# schematicEagle.net
KiCad netlist of a schematic drawn in EAGLE
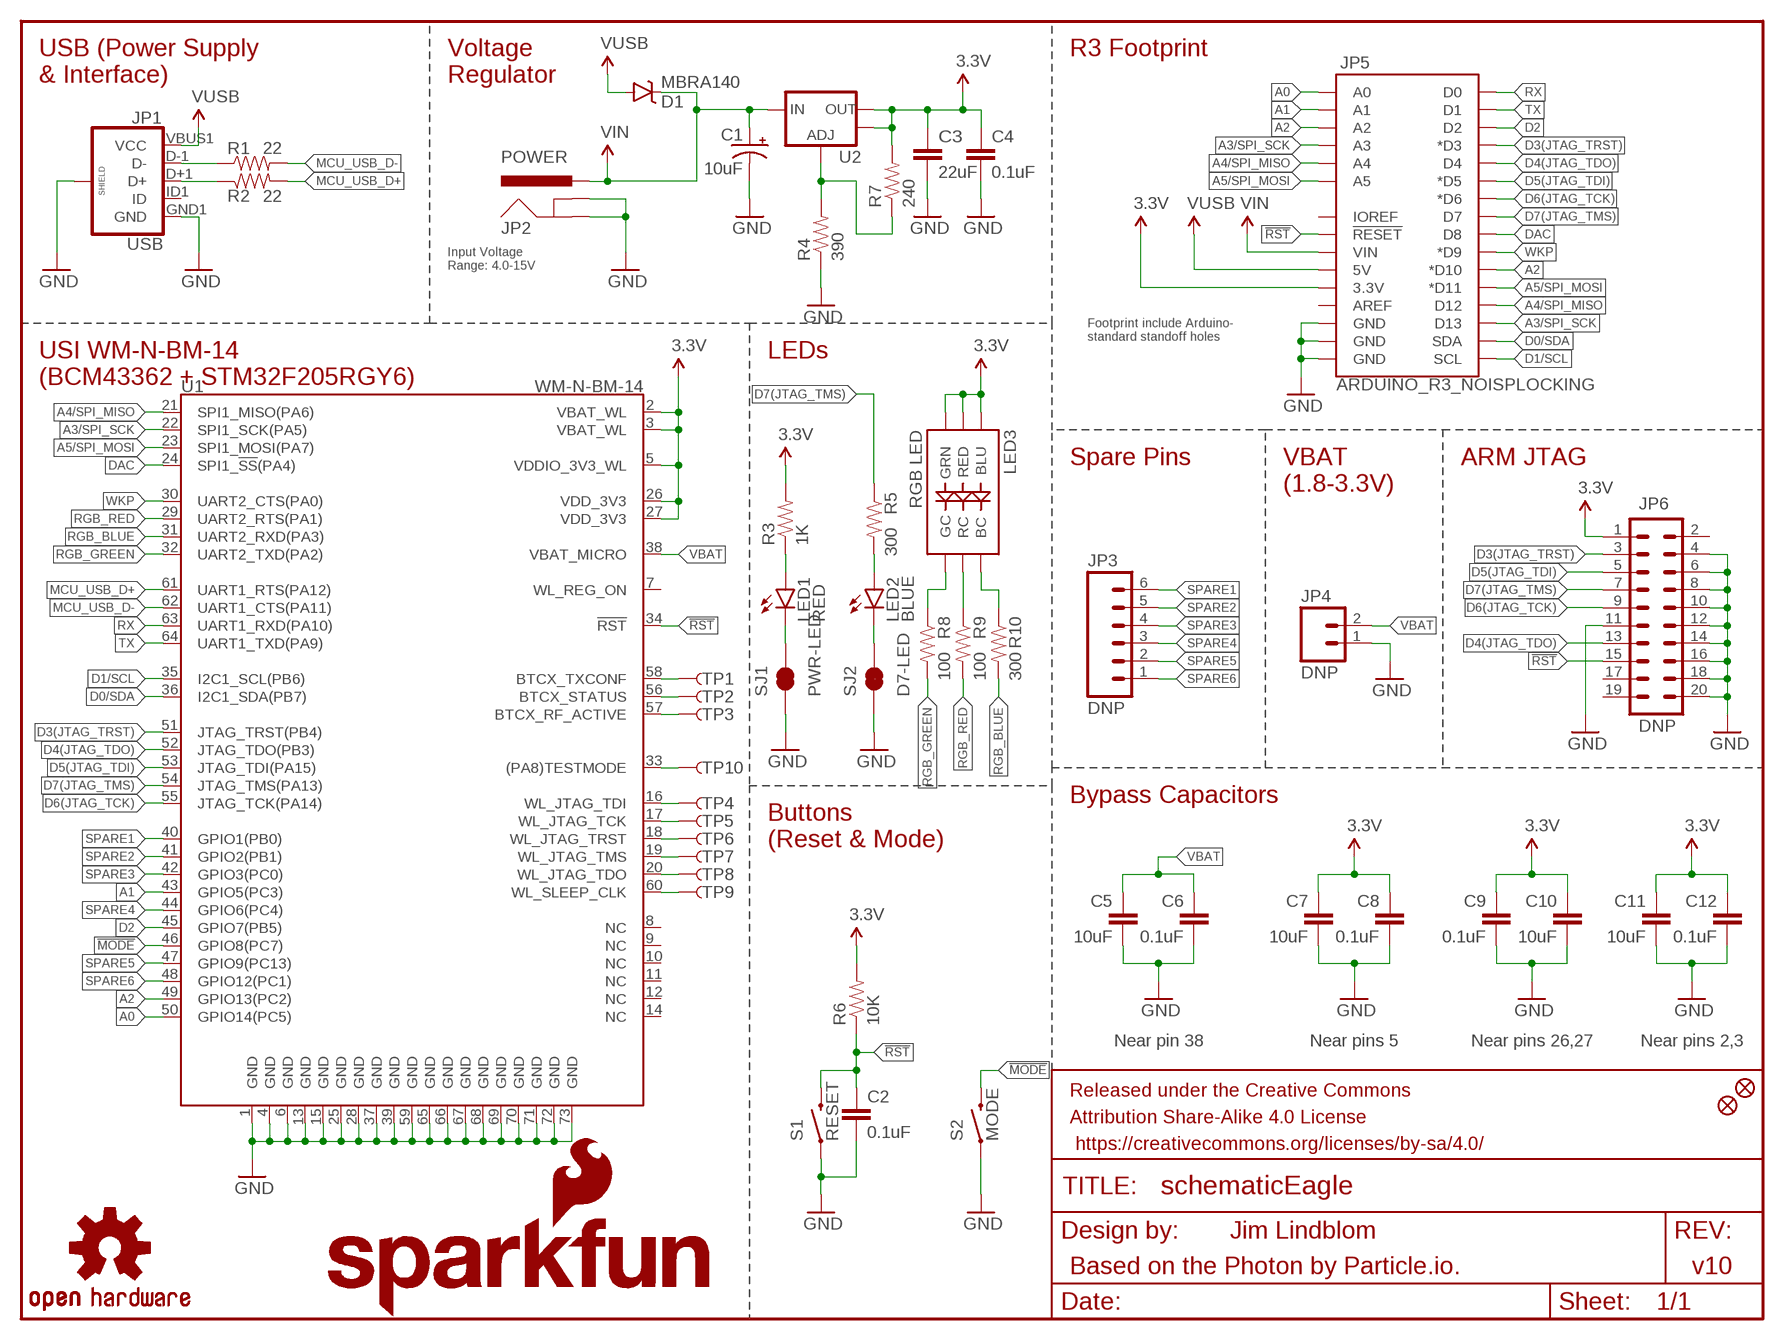
[diagram p0: schematic, sheet 1]

(export (version "E")
  (design (tool "Eeschema 10.0.6"))
  (components
    (comp (ref "C1")
      (value "10uF")
      (footprint "eagle-import:EIA3216")
      (libsource (lib "eagle-import") (part "10UF-16V-10%(TANT)"))
    )
    (comp (ref "C2")
      (value "0.1uF")
      (footprint "eagle-import:0603-CAP")
      (libsource (lib "eagle-import") (part "0.1UF-25V(+80/-20%)(0603)"))
    )
    (comp (ref "C3")
      (value "22uF")
      (footprint "eagle-import:0805")
      (libsource (lib "eagle-import") (part "22UF-6.3V-20%(0805)"))
    )
    (comp (ref "C4")
      (value "0.1uF")
      (footprint "eagle-import:0603-CAP")
      (libsource (lib "eagle-import") (part "0.1UF-25V(+80/-20%)(0603)"))
    )
    (comp (ref "C5")
      (value "10uF")
      (footprint "eagle-import:0603-CAP")
      (libsource (lib "eagle-import") (part "10UF-6.3V-20%(0603)"))
    )
    (comp (ref "C6")
      (value "0.1uF")
      (footprint "eagle-import:0603-CAP")
      (libsource (lib "eagle-import") (part "0.1UF-25V(+80/-20%)(0603)"))
    )
    (comp (ref "C7")
      (value "10uF")
      (footprint "eagle-import:0603-CAP")
      (libsource (lib "eagle-import") (part "10UF-6.3V-20%(0603)"))
    )
    (comp (ref "C8")
      (value "0.1uF")
      (footprint "eagle-import:0603-CAP")
      (libsource (lib "eagle-import") (part "0.1UF-25V(+80/-20%)(0603)"))
    )
    (comp (ref "C9")
      (value "0.1uF")
      (footprint "eagle-import:0603-CAP")
      (libsource (lib "eagle-import") (part "0.1UF-25V(+80/-20%)(0603)"))
    )
    (comp (ref "C10")
      (value "10uF")
      (footprint "eagle-import:0603-CAP")
      (libsource (lib "eagle-import") (part "10UF-6.3V-20%(0603)"))
    )
    (comp (ref "C11")
      (value "10uF")
      (footprint "eagle-import:0603-CAP")
      (libsource (lib "eagle-import") (part "10UF-6.3V-20%(0603)"))
    )
    (comp (ref "C12")
      (value "0.1uF")
      (footprint "eagle-import:0603-CAP")
      (libsource (lib "eagle-import") (part "0.1UF-25V(+80/-20%)(0603)"))
    )
    (comp (ref "D1")
      (value "MBRA140")
      (footprint "eagle-import:SMA-DIODE")
      (libsource (lib "eagle-import") (part "DIODE-SCHOTTKY-MBRA140"))
    )
    (comp (ref "FID1")
      (value "FIDUCIAL1X2")
      (footprint "eagle-import:FIDUCIAL-1X2")
      (libsource (lib "eagle-import") (part "FIDUCIAL1X2"))
    )
    (comp (ref "FID2")
      (value "FIDUCIAL1X2")
      (footprint "eagle-import:FIDUCIAL-1X2")
      (libsource (lib "eagle-import") (part "FIDUCIAL1X2"))
    )
    (comp (ref "FRAME1")
      (value "FRAME-LETTER")
      (footprint "eagle-import:CREATIVE_COMMONS")
      (fields (field (name "DESIGNER") "Jim Lindblom"))
      (libsource (lib "eagle-import") (part "FRAME-LETTER"))
    )
    (comp (ref "JP1")
      (value "USB")
      (footprint "eagle-import:USB-B-MICRO-SMD_V03")
      (libsource (lib "eagle-import") (part "USB_MICROB_PLUGCONN-11752"))
    )
    (comp (ref "JP2")
      (value "POWER")
      (footprint "eagle-import:POWER_JACK_PTH_LOCK")
      (libsource (lib "eagle-import") (part "POWER_JACKPTH_LOCK"))
    )
    (comp (ref "JP3")
      (value "DNP")
      (footprint "eagle-import:1X06")
      (libsource (lib "eagle-import") (part "M06SILK_FEMALE_PTH"))
    )
    (comp (ref "JP4")
      (value "DNP")
      (footprint "eagle-import:1X02")
      (libsource (lib "eagle-import") (part "M02PTH"))
    )
    (comp (ref "JP5")
      (value "ARDUINO_R3_NOISPLOCKING")
      (footprint "eagle-import:ARDUINO_R3_NOISP_LOCKING")
      (libsource (lib "eagle-import") (part "ARDUINO_R3_NOISPLOCKING"))
    )
    (comp (ref "JP6")
      (value "DNP")
      (footprint "eagle-import:2X10")
      (libsource (lib "eagle-import") (part "M10X2"))
    )
    (comp (ref "LED1")
      (value "RED")
      (footprint "eagle-import:LED-1206")
      (libsource (lib "eagle-import") (part "LED-RED1206"))
    )
    (comp (ref "LED2")
      (value "BLUE")
      (footprint "eagle-import:LED-1206")
      (libsource (lib "eagle-import") (part "LED-BLUE1206"))
    )
    (comp (ref "LED3")
      (value "RGB LED")
      (footprint "eagle-import:PLCC-6-LED")
      (libsource (lib "eagle-import") (part "LED-TRICOLOR-NO-COMPLCC-6-SMD"))
    )
    (comp (ref "LOGO1")
      (value "OSHW-LOGOM")
      (footprint "eagle-import:OSHW-LOGO-M")
      (libsource (lib "eagle-import") (part "OSHW-LOGOM"))
    )
    (comp (ref "LOGO2")
      (value "SFE_LOGO_NAME_FLAME.2_INCH")
      (footprint "eagle-import:SFE_LOGO_NAME_FLAME_.2")
      (libsource (lib "eagle-import") (part "SFE_LOGO_NAME_FLAME.2_INCH"))
    )
    (comp (ref "LOGO3")
      (value "SFE_LOGO_NAME_FLAME.4_INCH")
      (footprint "eagle-import:SFE_LOGO_NAME_FLAME_.4")
      (libsource (lib "eagle-import") (part "SFE_LOGO_NAME_FLAME.4_INCH"))
    )
    (comp (ref "R1")
      (value "22")
      (footprint "eagle-import:0603-RES")
      (libsource (lib "eagle-import") (part "22OHM1/10W1%(0603)"))
    )
    (comp (ref "R2")
      (value "22")
      (footprint "eagle-import:0603-RES")
      (libsource (lib "eagle-import") (part "22OHM1/10W1%(0603)"))
    )
    (comp (ref "R3")
      (value "1K")
      (footprint "eagle-import:0603-RES")
      (libsource (lib "eagle-import") (part "1KOHM-1/10W-1%(0603)"))
    )
    (comp (ref "R4")
      (value "390")
      (footprint "eagle-import:0603-RES")
      (libsource (lib "eagle-import") (part "390OHM1/10W1%(0603)"))
    )
    (comp (ref "R5")
      (value "300")
      (footprint "eagle-import:0603-RES")
      (libsource (lib "eagle-import") (part "300OHM-1/10W-1%(0603)"))
    )
    (comp (ref "R6")
      (value "10K")
      (footprint "eagle-import:0603-RES")
      (libsource (lib "eagle-import") (part "10KOHM-1/10W-1%(0603)0603"))
    )
    (comp (ref "R7")
      (value "240")
      (footprint "eagle-import:0603-RES")
      (libsource (lib "eagle-import") (part "240OHM1/10W1%(0603)"))
    )
    (comp (ref "R8")
      (value "100")
      (footprint "eagle-import:0603-RES")
      (libsource (lib "eagle-import") (part "100OHM-1/10W-1%(0603)"))
    )
    (comp (ref "R9")
      (value "100")
      (footprint "eagle-import:0603-RES")
      (libsource (lib "eagle-import") (part "100OHM-1/10W-1%(0603)"))
    )
    (comp (ref "R10")
      (value "300")
      (footprint "eagle-import:0603-RES")
      (libsource (lib "eagle-import") (part "300OHM-1/10W-1%(0603)"))
    )
    (comp (ref "S1")
      (value "RESET")
      (footprint "eagle-import:TACTILE-PTH")
      (libsource (lib "eagle-import") (part "SWITCH-MOMENTARY-2PTH"))
    )
    (comp (ref "S2")
      (value "MODE")
      (footprint "eagle-import:TACTILE-PTH")
      (libsource (lib "eagle-import") (part "SWITCH-MOMENTARY-2PTH"))
    )
    (comp (ref "SJ1")
      (value "PWR-LED")
      (footprint "eagle-import:PAD-JUMPER-2-NC_BY_TRACE_YES_SILK")
      (libsource (lib "eagle-import") (part "JUMPER-PAD-2-NC_BY_TRACE"))
    )
    (comp (ref "SJ2")
      (value "D7-LED")
      (footprint "eagle-import:PAD-JUMPER-2-NC_BY_TRACE_YES_SILK")
      (libsource (lib "eagle-import") (part "JUMPER-PAD-2-NC_BY_TRACE"))
    )
    (comp (ref "TP1")
      (value "TEST-POINTTP_15TH_THRU")
      (footprint "eagle-import:TP_15TH")
      (libsource (lib "eagle-import") (part "TEST-POINTTP_15TH_THRU"))
    )
    (comp (ref "TP2")
      (value "TEST-POINTTP_15TH_THRU")
      (footprint "eagle-import:TP_15TH")
      (libsource (lib "eagle-import") (part "TEST-POINTTP_15TH_THRU"))
    )
    (comp (ref "TP3")
      (value "TEST-POINTTP_15TH_THRU")
      (footprint "eagle-import:TP_15TH")
      (libsource (lib "eagle-import") (part "TEST-POINTTP_15TH_THRU"))
    )
    (comp (ref "TP4")
      (value "TEST-POINTTP_15TH_THRU")
      (footprint "eagle-import:TP_15TH")
      (libsource (lib "eagle-import") (part "TEST-POINTTP_15TH_THRU"))
    )
    (comp (ref "TP5")
      (value "TEST-POINTTP_15TH_THRU")
      (footprint "eagle-import:TP_15TH")
      (libsource (lib "eagle-import") (part "TEST-POINTTP_15TH_THRU"))
    )
    (comp (ref "TP6")
      (value "TEST-POINTTP_15TH_THRU")
      (footprint "eagle-import:TP_15TH")
      (libsource (lib "eagle-import") (part "TEST-POINTTP_15TH_THRU"))
    )
    (comp (ref "TP7")
      (value "TEST-POINTTP_15TH_THRU")
      (footprint "eagle-import:TP_15TH")
      (libsource (lib "eagle-import") (part "TEST-POINTTP_15TH_THRU"))
    )
    (comp (ref "TP8")
      (value "TEST-POINTTP_15TH_THRU")
      (footprint "eagle-import:TP_15TH")
      (libsource (lib "eagle-import") (part "TEST-POINTTP_15TH_THRU"))
    )
    (comp (ref "TP9")
      (value "TEST-POINTTP_15TH_THRU")
      (footprint "eagle-import:TP_15TH")
      (libsource (lib "eagle-import") (part "TEST-POINTTP_15TH_THRU"))
    )
    (comp (ref "TP10")
      (value "TEST-POINTTP_15TH_THRU")
      (footprint "eagle-import:TP_15TH")
      (libsource (lib "eagle-import") (part "TEST-POINTTP_15TH_THRU"))
    )
    (comp (ref "U1")
      (value "WM-N-BM-14")
      (footprint "eagle-import:WM-N-BM-14")
      (libsource (lib "eagle-import") (part "WM-N-BM-14"))
    )
    (comp (ref "U2")
      (value "V_REG_LM1117SOT223")
      (footprint "eagle-import:SOT223")
      (libsource (lib "eagle-import") (part "V_REG_LM1117SOT223"))
    )
  )
  (nets
    (net (code "1") (name "/~{MODE}") (class "Default")
      (node (ref "S2") (pin "3") (pinfunction "2_3") (pintype "passive"))
      (node (ref "U1") (pin "46") (pinfunction "GPIO8(PC7)_46") (pintype "bidirectional"))
    )
    (net (code "2") (name "/~{RST}") (class "Default")
      (node (ref "C2") (pin "1") (pinfunction "1_1") (pintype "passive"))
      (node (ref "JP5") (pin "RESET@1") (pinfunction "~{RESET}_RESET@1") (pintype "bidirectional"))
      (node (ref "JP6") (pin "15") (pinfunction "15_15") (pintype "passive"))
      (node (ref "R6") (pin "1") (pinfunction "1_1") (pintype "passive"))
      (node (ref "S1") (pin "3") (pinfunction "2_3") (pintype "passive"))
      (node (ref "U1") (pin "34") (pinfunction "~{RST}_34") (pintype "bidirectional"))
    )
    (net (code "3") (name "3.3V") (class "Default")
      (node (ref "C10") (pin "1") (pinfunction "1_1") (pintype "passive"))
      (node (ref "C11") (pin "1") (pinfunction "1_1") (pintype "passive"))
      (node (ref "C12") (pin "1") (pinfunction "1_1") (pintype "passive"))
      (node (ref "C3") (pin "1") (pinfunction "1_1") (pintype "passive"))
      (node (ref "C4") (pin "1") (pinfunction "1_1") (pintype "passive"))
      (node (ref "C7") (pin "1") (pinfunction "1_1") (pintype "passive"))
      (node (ref "C8") (pin "1") (pinfunction "1_1") (pintype "passive"))
      (node (ref "C9") (pin "1") (pinfunction "1_1") (pintype "passive"))
      (node (ref "JP5") (pin "3.3V") (pinfunction "3.3V_3.3V") (pintype "bidirectional"))
      (node (ref "JP6") (pin "1") (pinfunction "1_1") (pintype "passive"))
      (node (ref "LED3") (pin "AB") (pinfunction "BLU_AB") (pintype "bidirectional"))
      (node (ref "LED3") (pin "AG") (pinfunction "GRN_AG") (pintype "bidirectional"))
      (node (ref "LED3") (pin "AR") (pinfunction "RED_AR") (pintype "bidirectional"))
      (node (ref "R3") (pin "2") (pinfunction "2_2") (pintype "passive"))
      (node (ref "R6") (pin "2") (pinfunction "2_2") (pintype "passive"))
      (node (ref "R7") (pin "2") (pinfunction "2_2") (pintype "passive"))
      (node (ref "U1") (pin "2") (pinfunction "VBAT_WL_2") (pintype "bidirectional"))
      (node (ref "U1") (pin "26") (pinfunction "VDD_3V3_26") (pintype "bidirectional"))
      (node (ref "U1") (pin "27") (pinfunction "VDD_3V3_27") (pintype "bidirectional"))
      (node (ref "U1") (pin "3") (pinfunction "VBAT_WL_3") (pintype "bidirectional"))
      (node (ref "U1") (pin "5") (pinfunction "VDDIO_3V3_WL_5") (pintype "bidirectional"))
      (node (ref "U2") (pin "2") (pinfunction "OUT_2") (pintype "output"))
      (node (ref "U2") (pin "4") (pinfunction "OUT_4") (pintype "output"))
    )
    (net (code "4") (name "A0") (class "Default")
      (node (ref "JP5") (pin "A0") (pinfunction "A0_A0") (pintype "bidirectional"))
      (node (ref "U1") (pin "50") (pinfunction "GPIO14(PC5)_50") (pintype "bidirectional"))
    )
    (net (code "5") (name "A1") (class "Default")
      (node (ref "JP5") (pin "A1") (pinfunction "A1_A1") (pintype "bidirectional"))
      (node (ref "U1") (pin "43") (pinfunction "GPIO5(PC3)_43") (pintype "bidirectional"))
    )
    (net (code "6") (name "A2") (class "Default")
      (node (ref "JP5") (pin "A2") (pinfunction "A2_A2") (pintype "bidirectional"))
      (node (ref "JP5") (pin "D10") (pinfunction "*D10_D10") (pintype "bidirectional"))
      (node (ref "U1") (pin "49") (pinfunction "GPIO13(PC2)_49") (pintype "bidirectional"))
    )
    (net (code "7") (name "A3{slash}SPI_SCK") (class "Default")
      (node (ref "JP5") (pin "A3") (pinfunction "A3_A3") (pintype "bidirectional"))
      (node (ref "JP5") (pin "D13") (pinfunction "D13_D13") (pintype "bidirectional"))
      (node (ref "U1") (pin "22") (pinfunction "SPI1_SCK(PA5)_22") (pintype "bidirectional"))
    )
    (net (code "8") (name "A4{slash}SPI_MISO") (class "Default")
      (node (ref "JP5") (pin "A4") (pinfunction "A4_A4") (pintype "bidirectional"))
      (node (ref "JP5") (pin "D12") (pinfunction "D12_D12") (pintype "bidirectional"))
      (node (ref "U1") (pin "21") (pinfunction "SPI1_MISO(PA6)_21") (pintype "bidirectional"))
    )
    (net (code "9") (name "A5{slash}SPI_MOSI") (class "Default")
      (node (ref "JP5") (pin "A5") (pinfunction "A5_A5") (pintype "bidirectional"))
      (node (ref "JP5") (pin "D11") (pinfunction "*D11_D11") (pintype "bidirectional"))
      (node (ref "U1") (pin "23") (pinfunction "SPI1_MOSI(PA7)_23") (pintype "bidirectional"))
    )
    (net (code "10") (name "D0{slash}SDA") (class "Default")
      (node (ref "JP5") (pin "SDA") (pinfunction "SDA_SDA") (pintype "bidirectional"))
      (node (ref "U1") (pin "36") (pinfunction "I2C1_SDA(PB7)_36") (pintype "bidirectional"))
    )
    (net (code "11") (name "D1{slash}SCL") (class "Default")
      (node (ref "JP5") (pin "SCL") (pinfunction "SCL_SCL") (pintype "bidirectional"))
      (node (ref "U1") (pin "35") (pinfunction "I2C1_SCL(PB6)_35") (pintype "bidirectional"))
    )
    (net (code "12") (name "D2") (class "Default")
      (node (ref "JP5") (pin "D2") (pinfunction "D2_D2") (pintype "bidirectional"))
      (node (ref "U1") (pin "45") (pinfunction "GPIO7(PB5)_45") (pintype "bidirectional"))
    )
    (net (code "13") (name "D3(JTAG_TRST)") (class "Default")
      (node (ref "JP5") (pin "D3") (pinfunction "*D3_D3") (pintype "bidirectional"))
      (node (ref "JP6") (pin "3") (pinfunction "3_3") (pintype "passive"))
      (node (ref "U1") (pin "51") (pinfunction "JTAG_TRST(PB4)_51") (pintype "bidirectional"))
    )
    (net (code "14") (name "D4(JTAG_TDO)") (class "Default")
      (node (ref "JP5") (pin "D4") (pinfunction "D4_D4") (pintype "bidirectional"))
      (node (ref "JP6") (pin "13") (pinfunction "13_13") (pintype "passive"))
      (node (ref "U1") (pin "52") (pinfunction "JTAG_TDO(PB3)_52") (pintype "bidirectional"))
    )
    (net (code "15") (name "D5(JTAG_TDI)") (class "Default")
      (node (ref "JP5") (pin "D5") (pinfunction "*D5_D5") (pintype "bidirectional"))
      (node (ref "JP6") (pin "5") (pinfunction "5_5") (pintype "passive"))
      (node (ref "U1") (pin "53") (pinfunction "JTAG_TDI(PA15)_53") (pintype "bidirectional"))
    )
    (net (code "16") (name "D6(JTAG_TCK)") (class "Default")
      (node (ref "JP5") (pin "D6") (pinfunction "*D6_D6") (pintype "bidirectional"))
      (node (ref "JP6") (pin "9") (pinfunction "9_9") (pintype "passive"))
      (node (ref "U1") (pin "55") (pinfunction "JTAG_TCK(PA14)_55") (pintype "bidirectional"))
    )
    (net (code "17") (name "D7(JTAG_TMS)") (class "Default")
      (node (ref "JP5") (pin "D7") (pinfunction "D7_D7") (pintype "bidirectional"))
      (node (ref "JP6") (pin "7") (pinfunction "7_7") (pintype "passive"))
      (node (ref "R5") (pin "1") (pinfunction "1_1") (pintype "passive"))
      (node (ref "U1") (pin "54") (pinfunction "JTAG_TMS(PA13)_54") (pintype "bidirectional"))
    )
    (net (code "18") (name "DAC") (class "Default")
      (node (ref "JP5") (pin "D8") (pinfunction "D8_D8") (pintype "bidirectional"))
      (node (ref "U1") (pin "24") (pinfunction "SPI1_~{SS}(PA4)_24") (pintype "bidirectional"))
    )
    (net (code "19") (name "GND") (class "Default")
      (node (ref "C1") (pin "C") (pinfunction "-_C") (pintype "passive"))
      (node (ref "C10") (pin "2") (pinfunction "2_2") (pintype "passive"))
      (node (ref "C11") (pin "2") (pinfunction "2_2") (pintype "passive"))
      (node (ref "C12") (pin "2") (pinfunction "2_2") (pintype "passive"))
      (node (ref "C2") (pin "2") (pinfunction "2_2") (pintype "passive"))
      (node (ref "C3") (pin "2") (pinfunction "2_2") (pintype "passive"))
      (node (ref "C4") (pin "2") (pinfunction "2_2") (pintype "passive"))
      (node (ref "C5") (pin "2") (pinfunction "2_2") (pintype "passive"))
      (node (ref "C6") (pin "2") (pinfunction "2_2") (pintype "passive"))
      (node (ref "C7") (pin "2") (pinfunction "2_2") (pintype "passive"))
      (node (ref "C8") (pin "2") (pinfunction "2_2") (pintype "passive"))
      (node (ref "C9") (pin "2") (pinfunction "2_2") (pintype "passive"))
      (node (ref "JP1") (pin "GND1") (pinfunction "GND_GND1") (pintype "bidirectional"))
      (node (ref "JP1") (pin "SHIELD1") (pinfunction "SHIELD_SHIELD1") (pintype "bidirectional"))
      (node (ref "JP1") (pin "SHIELD2") (pinfunction "SHIELD_SHIELD2") (pintype "bidirectional"))
      (node (ref "JP1") (pin "SHIELD3") (pinfunction "SHIELD_SHIELD3") (pintype "bidirectional"))
      (node (ref "JP2") (pin "GND") (pinfunction "GND_GND") (pintype "bidirectional"))
      (node (ref "JP2") (pin "GNDBREAK") (pinfunction "GNDBREAK_GNDBREAK") (pintype "bidirectional"))
      (node (ref "JP4") (pin "1") (pinfunction "1_1") (pintype "passive"))
      (node (ref "JP5") (pin "GND@1") (pinfunction "GND_GND@1") (pintype "bidirectional"))
      (node (ref "JP5") (pin "GND@2") (pinfunction "GND_GND@2") (pintype "bidirectional"))
      (node (ref "JP5") (pin "GND@3") (pinfunction "GND_GND@3") (pintype "bidirectional"))
      (node (ref "JP6") (pin "10") (pinfunction "10_10") (pintype "passive"))
      (node (ref "JP6") (pin "11") (pinfunction "11_11") (pintype "passive"))
      (node (ref "JP6") (pin "12") (pinfunction "12_12") (pintype "passive"))
      (node (ref "JP6") (pin "14") (pinfunction "14_14") (pintype "passive"))
      (node (ref "JP6") (pin "16") (pinfunction "16_16") (pintype "passive"))
      (node (ref "JP6") (pin "18") (pinfunction "18_18") (pintype "passive"))
      (node (ref "JP6") (pin "20") (pinfunction "20_20") (pintype "passive"))
      (node (ref "JP6") (pin "4") (pinfunction "4_4") (pintype "passive"))
      (node (ref "JP6") (pin "6") (pinfunction "6_6") (pintype "passive"))
      (node (ref "JP6") (pin "8") (pinfunction "8_8") (pintype "passive"))
      (node (ref "R4") (pin "1") (pinfunction "1_1") (pintype "passive"))
      (node (ref "S1") (pin "1") (pinfunction "1_1") (pintype "passive"))
      (node (ref "S2") (pin "1") (pinfunction "1_1") (pintype "passive"))
      (node (ref "SJ1") (pin "1") (pinfunction "1_1") (pintype "passive"))
      (node (ref "SJ2") (pin "1") (pinfunction "1_1") (pintype "passive"))
      (node (ref "U1") (pin "1") (pinfunction "GND_1") (pintype "bidirectional"))
      (node (ref "U1") (pin "13") (pinfunction "GND_13") (pintype "bidirectional"))
      (node (ref "U1") (pin "15") (pinfunction "GND_15") (pintype "bidirectional"))
      (node (ref "U1") (pin "25") (pinfunction "GND_25") (pintype "bidirectional"))
      (node (ref "U1") (pin "28") (pinfunction "GND_28") (pintype "bidirectional"))
      (node (ref "U1") (pin "37") (pinfunction "GND_37") (pintype "bidirectional"))
      (node (ref "U1") (pin "39") (pinfunction "GND_39") (pintype "bidirectional"))
      (node (ref "U1") (pin "4") (pinfunction "GND_4") (pintype "bidirectional"))
      (node (ref "U1") (pin "59") (pinfunction "GND_59") (pintype "bidirectional"))
      (node (ref "U1") (pin "6") (pinfunction "GND_6") (pintype "bidirectional"))
      (node (ref "U1") (pin "65") (pinfunction "GND_65") (pintype "bidirectional"))
      (node (ref "U1") (pin "66") (pinfunction "GND_66") (pintype "bidirectional"))
      (node (ref "U1") (pin "67") (pinfunction "GND_67") (pintype "bidirectional"))
      (node (ref "U1") (pin "68") (pinfunction "GND_68") (pintype "bidirectional"))
      (node (ref "U1") (pin "69") (pinfunction "GND_69") (pintype "bidirectional"))
      (node (ref "U1") (pin "70") (pinfunction "GND_70") (pintype "bidirectional"))
      (node (ref "U1") (pin "71") (pinfunction "GND_71") (pintype "bidirectional"))
      (node (ref "U1") (pin "72") (pinfunction "GND_72") (pintype "bidirectional"))
      (node (ref "U1") (pin "73") (pinfunction "GND_73") (pintype "bidirectional"))
    )
    (net (code "20") (name "MCU_USB_D+") (class "Default")
      (node (ref "R2") (pin "2") (pinfunction "2_2") (pintype "passive"))
      (node (ref "U1") (pin "61") (pinfunction "UART1_RTS(PA12)_61") (pintype "bidirectional"))
    )
    (net (code "21") (name "MCU_USB_D-") (class "Default")
      (node (ref "R1") (pin "2") (pinfunction "2_2") (pintype "passive"))
      (node (ref "U1") (pin "62") (pinfunction "UART1_CTS(PA11)_62") (pintype "bidirectional"))
    )
    (net (code "22") (name "Net-(JP1-D+)") (class "Default")
      (node (ref "JP1") (pin "D+1") (pinfunction "D+_D+1") (pintype "bidirectional"))
      (node (ref "R2") (pin "1") (pinfunction "1_1") (pintype "passive"))
    )
    (net (code "23") (name "Net-(JP1-D-)") (class "Default")
      (node (ref "JP1") (pin "D-1") (pinfunction "D-_D-1") (pintype "bidirectional"))
      (node (ref "R1") (pin "1") (pinfunction "1_1") (pintype "passive"))
    )
    (net (code "24") (name "Net-(LED1-PadA)") (class "Default")
      (node (ref "LED1") (pin "A") (pinfunction "A_A") (pintype "passive"))
      (node (ref "R3") (pin "1") (pinfunction "1_1") (pintype "passive"))
    )
    (net (code "25") (name "Net-(LED1-PadC)") (class "Default")
      (node (ref "LED1") (pin "C") (pinfunction "C_C") (pintype "passive"))
      (node (ref "SJ1") (pin "2") (pinfunction "2_2") (pintype "passive"))
    )
    (net (code "26") (name "Net-(LED2-PadA)") (class "Default")
      (node (ref "LED2") (pin "A") (pinfunction "A_A") (pintype "passive"))
      (node (ref "R5") (pin "2") (pinfunction "2_2") (pintype "passive"))
    )
    (net (code "27") (name "Net-(LED2-PadC)") (class "Default")
      (node (ref "LED2") (pin "C") (pinfunction "C_C") (pintype "passive"))
      (node (ref "SJ2") (pin "2") (pinfunction "2_2") (pintype "passive"))
    )
    (net (code "28") (name "Net-(LED3-BC)") (class "Default")
      (node (ref "LED3") (pin "CB") (pinfunction "BC_CB") (pintype "bidirectional"))
      (node (ref "R10") (pin "1") (pinfunction "1_1") (pintype "passive"))
    )
    (net (code "29") (name "Net-(LED3-GC)") (class "Default")
      (node (ref "LED3") (pin "CG") (pinfunction "GC_CG") (pintype "bidirectional"))
      (node (ref "R8") (pin "1") (pinfunction "1_1") (pintype "passive"))
    )
    (net (code "30") (name "Net-(LED3-RC)") (class "Default")
      (node (ref "LED3") (pin "CR") (pinfunction "RC_CR") (pintype "bidirectional"))
      (node (ref "R9") (pin "1") (pinfunction "1_1") (pintype "passive"))
    )
    (net (code "31") (name "Net-(TP1-1)") (class "Default")
      (node (ref "TP1") (pin "P$1") (pinfunction "1_P$1") (pintype "bidirectional"))
      (node (ref "U1") (pin "58") (pinfunction "BTCX_TXCONF_58") (pintype "bidirectional"))
    )
    (net (code "32") (name "Net-(TP2-1)") (class "Default")
      (node (ref "TP2") (pin "P$1") (pinfunction "1_P$1") (pintype "bidirectional"))
      (node (ref "U1") (pin "56") (pinfunction "BTCX_STATUS_56") (pintype "bidirectional"))
    )
    (net (code "33") (name "Net-(TP3-1)") (class "Default")
      (node (ref "TP3") (pin "P$1") (pinfunction "1_P$1") (pintype "bidirectional"))
      (node (ref "U1") (pin "57") (pinfunction "BTCX_RF_ACTIVE_57") (pintype "bidirectional"))
    )
    (net (code "34") (name "Net-(TP4-1)") (class "Default")
      (node (ref "TP4") (pin "P$1") (pinfunction "1_P$1") (pintype "bidirectional"))
      (node (ref "U1") (pin "16") (pinfunction "WL_JTAG_TDI_16") (pintype "bidirectional"))
    )
    (net (code "35") (name "Net-(TP5-1)") (class "Default")
      (node (ref "TP5") (pin "P$1") (pinfunction "1_P$1") (pintype "bidirectional"))
      (node (ref "U1") (pin "17") (pinfunction "WL_JTAG_TCK_17") (pintype "bidirectional"))
    )
    (net (code "36") (name "Net-(TP6-1)") (class "Default")
      (node (ref "TP6") (pin "P$1") (pinfunction "1_P$1") (pintype "bidirectional"))
      (node (ref "U1") (pin "18") (pinfunction "WL_JTAG_TRST_18") (pintype "bidirectional"))
    )
    (net (code "37") (name "Net-(TP7-1)") (class "Default")
      (node (ref "TP7") (pin "P$1") (pinfunction "1_P$1") (pintype "bidirectional"))
      (node (ref "U1") (pin "19") (pinfunction "WL_JTAG_TMS_19") (pintype "bidirectional"))
    )
    (net (code "38") (name "Net-(TP8-1)") (class "Default")
      (node (ref "TP8") (pin "P$1") (pinfunction "1_P$1") (pintype "bidirectional"))
      (node (ref "U1") (pin "20") (pinfunction "WL_JTAG_TDO_20") (pintype "bidirectional"))
    )
    (net (code "39") (name "Net-(TP9-1)") (class "Default")
      (node (ref "TP9") (pin "P$1") (pinfunction "1_P$1") (pintype "bidirectional"))
      (node (ref "U1") (pin "60") (pinfunction "WL_SLEEP_CLK_60") (pintype "bidirectional"))
    )
    (net (code "40") (name "Net-(TP10-1)") (class "Default")
      (node (ref "TP10") (pin "P$1") (pinfunction "1_P$1") (pintype "bidirectional"))
      (node (ref "U1") (pin "33") (pinfunction "(PA8)TESTMODE_33") (pintype "bidirectional"))
    )
    (net (code "41") (name "Net-(U2-ADJ)") (class "Default")
      (node (ref "R4") (pin "2") (pinfunction "2_2") (pintype "passive"))
      (node (ref "R7") (pin "1") (pinfunction "1_1") (pintype "passive"))
      (node (ref "U2") (pin "1") (pinfunction "ADJ_1") (pintype "input"))
    )
    (net (code "42") (name "RGB_BLUE") (class "Default")
      (node (ref "R10") (pin "2") (pinfunction "2_2") (pintype "passive"))
      (node (ref "U1") (pin "31") (pinfunction "UART2_RXD(PA3)_31") (pintype "bidirectional"))
    )
    (net (code "43") (name "RGB_GREEN") (class "Default")
      (node (ref "R8") (pin "2") (pinfunction "2_2") (pintype "passive"))
      (node (ref "U1") (pin "32") (pinfunction "UART2_TXD(PA2)_32") (pintype "bidirectional"))
    )
    (net (code "44") (name "RGB_RED") (class "Default")
      (node (ref "R9") (pin "2") (pinfunction "2_2") (pintype "passive"))
      (node (ref "U1") (pin "29") (pinfunction "UART2_RTS(PA1)_29") (pintype "bidirectional"))
    )
    (net (code "45") (name "RX") (class "Default")
      (node (ref "JP5") (pin "D0") (pinfunction "D0_D0") (pintype "bidirectional"))
      (node (ref "U1") (pin "63") (pinfunction "UART1_RXD(PA10)_63") (pintype "bidirectional"))
    )
    (net (code "46") (name "SPARE1") (class "Default")
      (node (ref "JP3") (pin "6") (pinfunction "6_6") (pintype "passive"))
      (node (ref "U1") (pin "40") (pinfunction "GPIO1(PB0)_40") (pintype "bidirectional"))
    )
    (net (code "47") (name "SPARE2") (class "Default")
      (node (ref "JP3") (pin "5") (pinfunction "5_5") (pintype "passive"))
      (node (ref "U1") (pin "41") (pinfunction "GPIO2(PB1)_41") (pintype "bidirectional"))
    )
    (net (code "48") (name "SPARE3") (class "Default")
      (node (ref "JP3") (pin "4") (pinfunction "4_4") (pintype "passive"))
      (node (ref "U1") (pin "42") (pinfunction "GPIO3(PC0)_42") (pintype "bidirectional"))
    )
    (net (code "49") (name "SPARE4") (class "Default")
      (node (ref "JP3") (pin "3") (pinfunction "3_3") (pintype "passive"))
      (node (ref "U1") (pin "44") (pinfunction "GPIO6(PC4)_44") (pintype "bidirectional"))
    )
    (net (code "50") (name "SPARE5") (class "Default")
      (node (ref "JP3") (pin "2") (pinfunction "2_2") (pintype "passive"))
      (node (ref "U1") (pin "47") (pinfunction "GPIO9(PC13)_47") (pintype "bidirectional"))
    )
    (net (code "51") (name "SPARE6") (class "Default")
      (node (ref "JP3") (pin "1") (pinfunction "1_1") (pintype "passive"))
      (node (ref "U1") (pin "48") (pinfunction "GPIO12(PC1)_48") (pintype "bidirectional"))
    )
    (net (code "52") (name "TX") (class "Default")
      (node (ref "JP5") (pin "D1") (pinfunction "D1_D1") (pintype "bidirectional"))
      (node (ref "U1") (pin "64") (pinfunction "UART1_TXD(PA9)_64") (pintype "bidirectional"))
    )
    (net (code "53") (name "VBAT") (class "Default")
      (node (ref "C5") (pin "1") (pinfunction "1_1") (pintype "passive"))
      (node (ref "C6") (pin "1") (pinfunction "1_1") (pintype "passive"))
      (node (ref "JP4") (pin "2") (pinfunction "2_2") (pintype "passive"))
      (node (ref "U1") (pin "38") (pinfunction "VBAT_MICRO_38") (pintype "bidirectional"))
    )
    (net (code "54") (name "VIN") (class "Default")
      (node (ref "C1") (pin "A") (pinfunction "+_A") (pintype "passive"))
      (node (ref "D1") (pin "C") (pinfunction "C_C") (pintype "passive"))
      (node (ref "JP2") (pin "PWR") (pinfunction "PWR_PWR") (pintype "bidirectional"))
      (node (ref "JP5") (pin "VIN") (pinfunction "VIN_VIN") (pintype "bidirectional"))
      (node (ref "U2") (pin "3") (pinfunction "IN_3") (pintype "input"))
    )
    (net (code "55") (name "VUSB") (class "Default")
      (node (ref "D1") (pin "A") (pinfunction "A_A") (pintype "passive"))
      (node (ref "JP1") (pin "VBUS1") (pinfunction "VCC_VBUS1") (pintype "bidirectional"))
      (node (ref "JP5") (pin "5V") (pinfunction "5V_5V") (pintype "bidirectional"))
    )
    (net (code "56") (name "WKP") (class "Default")
      (node (ref "JP5") (pin "D9") (pinfunction "*D9_D9") (pintype "bidirectional"))
      (node (ref "U1") (pin "30") (pinfunction "UART2_CTS(PA0)_30") (pintype "bidirectional"))
    )
    (net (code "57") (name "unconnected-(JP1-ID-PadID1)") (class "Default")
      (node (ref "JP1") (pin "ID1") (pinfunction "ID_ID1") (pintype "bidirectional"))
    )
    (net (code "58") (name "unconnected-(JP5-PadAREF)") (class "Default")
      (node (ref "JP5") (pin "AREF") (pinfunction "AREF_AREF") (pintype "bidirectional"))
    )
    (net (code "59") (name "unconnected-(JP5-PadIOREF)") (class "Default")
      (node (ref "JP5") (pin "IOREF") (pinfunction "IOREF_IOREF") (pintype "bidirectional"))
    )
    (net (code "60") (name "unconnected-(JP6-Pad2)") (class "Default")
      (node (ref "JP6") (pin "2") (pinfunction "2_2") (pintype "passive"))
    )
    (net (code "61") (name "unconnected-(JP6-Pad17)") (class "Default")
      (node (ref "JP6") (pin "17") (pinfunction "17_17") (pintype "passive"))
    )
    (net (code "62") (name "unconnected-(JP6-Pad19)") (class "Default")
      (node (ref "JP6") (pin "19") (pinfunction "19_19") (pintype "passive"))
    )
    (net (code "63") (name "unconnected-(U1-NC-Pad8)") (class "Default")
      (node (ref "U1") (pin "8") (pinfunction "NC_8") (pintype "bidirectional"))
    )
    (net (code "64") (name "unconnected-(U1-NC-Pad9)") (class "Default")
      (node (ref "U1") (pin "9") (pinfunction "NC_9") (pintype "bidirectional"))
    )
    (net (code "65") (name "unconnected-(U1-NC-Pad10)") (class "Default")
      (node (ref "U1") (pin "10") (pinfunction "NC_10") (pintype "bidirectional"))
    )
    (net (code "66") (name "unconnected-(U1-NC-Pad11)") (class "Default")
      (node (ref "U1") (pin "11") (pinfunction "NC_11") (pintype "bidirectional"))
    )
    (net (code "67") (name "unconnected-(U1-NC-Pad12)") (class "Default")
      (node (ref "U1") (pin "12") (pinfunction "NC_12") (pintype "bidirectional"))
    )
    (net (code "68") (name "unconnected-(U1-NC-Pad14)") (class "Default")
      (node (ref "U1") (pin "14") (pinfunction "NC_14") (pintype "bidirectional"))
    )
    (net (code "69") (name "unconnected-(U1-WL_REG_ON-Pad7)") (class "Default")
      (node (ref "U1") (pin "7") (pinfunction "WL_REG_ON_7") (pintype "bidirectional"))
    )
  )
)
